# Output.net
KiCad netlist of a schematic drawn in Altium Designer
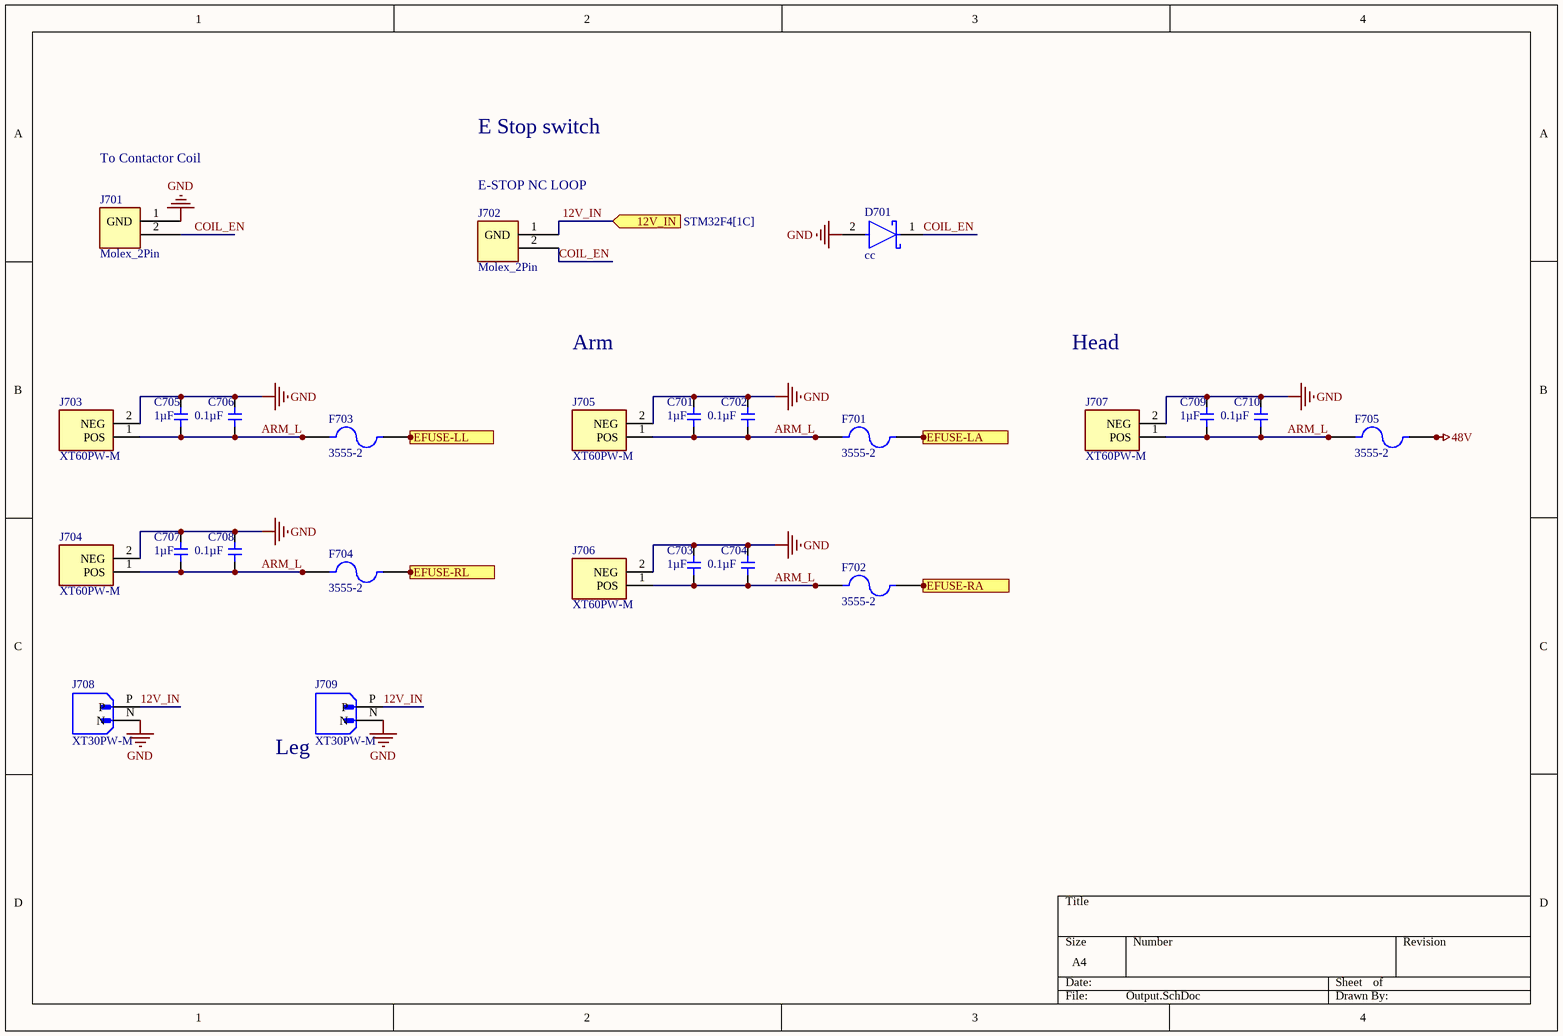
[diagram p0: Output.SchDoc]

(export (version "E")
  (design (tool "Eeschema 10.0.6"))
  (components
    (comp (ref "C701")
      (value "non-polar_Capacitor")
      (footprint "0805")
      (description "SMD type ceramic capacitor")
      (fields
        (field (name "VOLTAGE") "100V")
        (field (name "CAPACITANCE") "1µF")
        (field (name "SOURCE") "robit_passive.SchLib")
      )
      (libsource (lib "robit circuit") (part "Capacitor"))
    )
    (comp (ref "C702")
      (value "non-polar_Capacitor")
      (footprint "0603")
      (description "SMD type ceramic capacitor")
      (fields
        (field (name "VOLTAGE") "100V")
        (field (name "CAPACITANCE") "0.1µF")
        (field (name "SOURCE") "robit_passive.SchLib")
      )
      (libsource (lib "robit circuit") (part "Capacitor"))
    )
    (comp (ref "C703")
      (value "non-polar_Capacitor")
      (footprint "0805")
      (description "SMD type ceramic capacitor")
      (fields
        (field (name "VOLTAGE") "100V")
        (field (name "CAPACITANCE") "1µF")
        (field (name "SOURCE") "robit_passive.SchLib")
      )
      (libsource (lib "robit circuit") (part "Capacitor"))
    )
    (comp (ref "C704")
      (value "non-polar_Capacitor")
      (footprint "0603")
      (description "SMD type ceramic capacitor")
      (fields
        (field (name "VOLTAGE") "100V")
        (field (name "CAPACITANCE") "0.1µF")
        (field (name "SOURCE") "robit_passive.SchLib")
      )
      (libsource (lib "robit circuit") (part "Capacitor"))
    )
    (comp (ref "C705")
      (value "non-polar_Capacitor")
      (footprint "0805")
      (description "SMD type ceramic capacitor")
      (fields
        (field (name "VOLTAGE") "100V")
        (field (name "CAPACITANCE") "1µF")
        (field (name "SOURCE") "robit_passive.SchLib")
      )
      (libsource (lib "robit circuit") (part "Capacitor"))
    )
    (comp (ref "C706")
      (value "non-polar_Capacitor")
      (footprint "0603")
      (description "SMD type ceramic capacitor")
      (fields
        (field (name "VOLTAGE") "100V")
        (field (name "CAPACITANCE") "0.1µF")
        (field (name "SOURCE") "robit_passive.SchLib")
      )
      (libsource (lib "robit circuit") (part "Capacitor"))
    )
    (comp (ref "C707")
      (value "non-polar_Capacitor")
      (footprint "0805")
      (description "SMD type ceramic capacitor")
      (fields
        (field (name "VOLTAGE") "100V")
        (field (name "CAPACITANCE") "1µF")
        (field (name "SOURCE") "robit_passive.SchLib")
      )
      (libsource (lib "robit circuit") (part "Capacitor"))
    )
    (comp (ref "C708")
      (value "non-polar_Capacitor")
      (footprint "0603")
      (description "SMD type ceramic capacitor")
      (fields
        (field (name "VOLTAGE") "100V")
        (field (name "CAPACITANCE") "0.1µF")
        (field (name "SOURCE") "robit_passive.SchLib")
      )
      (libsource (lib "robit circuit") (part "Capacitor"))
    )
    (comp (ref "C709")
      (value "non-polar_Capacitor")
      (footprint "0805")
      (description "SMD type ceramic capacitor")
      (fields
        (field (name "VOLTAGE") "100V")
        (field (name "CAPACITANCE") "1µF")
        (field (name "SOURCE") "robit_passive.SchLib")
      )
      (libsource (lib "robit circuit") (part "Capacitor"))
    )
    (comp (ref "C710")
      (value "non-polar_Capacitor")
      (footprint "0603")
      (description "SMD type ceramic capacitor")
      (fields
        (field (name "VOLTAGE") "100V")
        (field (name "CAPACITANCE") "0.1µF")
        (field (name "SOURCE") "robit_passive.SchLib")
      )
      (libsource (lib "robit circuit") (part "Capacitor"))
    )
    (comp (ref "D701")
      (value "cc")
      (footprint "FP-403A-03-MFG")
      (description "Rectifier Diode, Schottky, 1 Phase, 1 Element, 5A, 100V V(RRM), Silicon")
      (libsource (lib "robit circuit") (part "1d6ec82d83fb6aee721767c19dac4b9"))
    )
    (comp (ref "F701")
      (value "3555-2")
      (footprint "FUSE_3555-2")
      (fields (field (name "MF") "Keystone Electronics"))
      (libsource (lib "3555-2 (1)") (part "3555-2"))
    )
    (comp (ref "F702")
      (value "3555-2")
      (footprint "FUSE_3555-2")
      (fields (field (name "MF") "Keystone Electronics"))
      (libsource (lib "3555-2 (1)") (part "3555-2"))
    )
    (comp (ref "F703")
      (value "3555-2")
      (footprint "FUSE_3555-2")
      (fields (field (name "MF") "Keystone Electronics"))
      (libsource (lib "3555-2 (1)") (part "3555-2"))
    )
    (comp (ref "F704")
      (value "3555-2")
      (footprint "FUSE_3555-2")
      (fields (field (name "MF") "Keystone Electronics"))
      (libsource (lib "3555-2 (1)") (part "3555-2"))
    )
    (comp (ref "F705")
      (value "3555-2")
      (footprint "FUSE_3555-2")
      (fields (field (name "MF") "Keystone Electronics"))
      (libsource (lib "3555-2 (1)") (part "3555-2"))
    )
    (comp (ref "J701")
      (value "Molex_2Pin")
      (footprint "MOLEX_2PIN")
      (description "Molex 2Pin Connector")
      (fields (field (name "SOURCE") "robit_connector.SchLib"))
      (libsource (lib "robit circuit") (part "Molex_2Pin"))
    )
    (comp (ref "J702")
      (value "Molex_2Pin")
      (footprint "MOLEX_2PIN")
      (description "Molex 2Pin Connector")
      (fields (field (name "SOURCE") "robit_connector.SchLib"))
      (libsource (lib "robit circuit") (part "Molex_2Pin"))
    )
    (comp (ref "J703")
      (value "XT60PW-M")
      (footprint "XT60PW-M")
      (description "Socket, DC supply, male, PIN: 2")
      (fields (field (name "MF") "AMASS") (field (name "SOURCE") "robit_connector.SchLib"))
      (libsource (lib "robit circuit") (part "XT60PW-M"))
    )
    (comp (ref "J704")
      (value "XT60PW-M")
      (footprint "XT60PW-M")
      (description "Socket, DC supply, male, PIN: 2")
      (fields (field (name "MF") "AMASS") (field (name "SOURCE") "robit_connector.SchLib"))
      (libsource (lib "robit circuit") (part "XT60PW-M"))
    )
    (comp (ref "J705")
      (value "XT60PW-M")
      (footprint "XT60PW-M")
      (description "Socket, DC supply, male, PIN: 2")
      (fields (field (name "MF") "AMASS") (field (name "SOURCE") "robit_connector.SchLib"))
      (libsource (lib "robit circuit") (part "XT60PW-M"))
    )
    (comp (ref "J706")
      (value "XT60PW-M")
      (footprint "XT60PW-M")
      (description "Socket, DC supply, male, PIN: 2")
      (fields (field (name "MF") "AMASS") (field (name "SOURCE") "robit_connector.SchLib"))
      (libsource (lib "robit circuit") (part "XT60PW-M"))
    )
    (comp (ref "J707")
      (value "XT60PW-M")
      (footprint "XT60PW-M")
      (description "Socket, DC supply, male, PIN: 2")
      (fields (field (name "MF") "AMASS") (field (name "SOURCE") "robit_connector.SchLib"))
      (libsource (lib "robit circuit") (part "XT60PW-M"))
    )
    (comp (ref "J708")
      (value "XT30PW-M")
      (footprint "AMASS_XT30PW-M")
      (description "Socket; DC supply; XT30; male; PIN: 2; on PCBs; THT; Colour: yellow")
      (fields (field (name "MF") "AMASS"))
      (libsource (lib "robit circuit") (part "XT30PW-M"))
    )
    (comp (ref "J709")
      (value "XT30PW-M")
      (footprint "AMASS_XT30PW-M")
      (description "Socket; DC supply; XT30; male; PIN: 2; on PCBs; THT; Colour: yellow")
      (fields (field (name "MF") "AMASS"))
      (libsource (lib "robit circuit") (part "XT30PW-M"))
    )
  )
  (nets
    (net (code "1") (name "/12V_IN") (class "Default")
      (node (ref "J702") (pin "1") (pinfunction "GND_1") (pintype "passive"))
      (node (ref "J708") (pin "P") (pinfunction "P_P") (pintype "passive"))
      (node (ref "J709") (pin "P") (pinfunction "P_P") (pintype "passive"))
    )
    (net (code "2") (name "/ARM_L") (class "Default")
      (node (ref "C701") (pin "1") (pinfunction "1_1") (pintype "passive"))
      (node (ref "C702") (pin "1") (pinfunction "1_1") (pintype "passive"))
      (node (ref "C703") (pin "1") (pinfunction "1_1") (pintype "passive"))
      (node (ref "C704") (pin "1") (pinfunction "1_1") (pintype "passive"))
      (node (ref "C705") (pin "1") (pinfunction "1_1") (pintype "passive"))
      (node (ref "C706") (pin "1") (pinfunction "1_1") (pintype "passive"))
      (node (ref "C707") (pin "1") (pinfunction "1_1") (pintype "passive"))
      (node (ref "C708") (pin "1") (pinfunction "1_1") (pintype "passive"))
      (node (ref "C709") (pin "1") (pinfunction "1_1") (pintype "passive"))
      (node (ref "C710") (pin "1") (pinfunction "1_1") (pintype "passive"))
      (node (ref "F701") (pin "1_1") (pinfunction "1_1_1") (pintype "passive"))
      (node (ref "F701") (pin "1_2") (pinfunction "1_1_2") (pintype "passive"))
      (node (ref "F702") (pin "1_1") (pinfunction "1_1_1") (pintype "passive"))
      (node (ref "F702") (pin "1_2") (pinfunction "1_1_2") (pintype "passive"))
      (node (ref "F703") (pin "1_1") (pinfunction "1_1_1") (pintype "passive"))
      (node (ref "F703") (pin "1_2") (pinfunction "1_1_2") (pintype "passive"))
      (node (ref "F704") (pin "1_1") (pinfunction "1_1_1") (pintype "passive"))
      (node (ref "F704") (pin "1_2") (pinfunction "1_1_2") (pintype "passive"))
      (node (ref "F705") (pin "1_1") (pinfunction "1_1_1") (pintype "passive"))
      (node (ref "F705") (pin "1_2") (pinfunction "1_1_2") (pintype "passive"))
      (node (ref "J703") (pin "1") (pinfunction "POS_1") (pintype "passive"))
      (node (ref "J704") (pin "1") (pinfunction "POS_1") (pintype "passive"))
      (node (ref "J705") (pin "1") (pinfunction "POS_1") (pintype "passive"))
      (node (ref "J706") (pin "1") (pinfunction "POS_1") (pintype "passive"))
      (node (ref "J707") (pin "1") (pinfunction "POS_1") (pintype "passive"))
    )
    (net (code "3") (name "/COIL_EN") (class "Default")
      (node (ref "D701") (pin "1") (pinfunction "C_1") (pintype "passive"))
      (node (ref "J701") (pin "2") (pintype "passive"))
      (node (ref "J702") (pin "2") (pintype "passive"))
    )
    (net (code "4") (name "/EFUSE-LA") (class "Default")
      (node (ref "F701") (pin "2_1") (pinfunction "2_2_1") (pintype "passive"))
      (node (ref "F701") (pin "2_2") (pinfunction "2_2_2") (pintype "passive"))
    )
    (net (code "5") (name "/EFUSE-LL") (class "Default")
      (node (ref "F703") (pin "2_1") (pinfunction "2_2_1") (pintype "passive"))
      (node (ref "F703") (pin "2_2") (pinfunction "2_2_2") (pintype "passive"))
    )
    (net (code "6") (name "/EFUSE-RA") (class "Default")
      (node (ref "F702") (pin "2_1") (pinfunction "2_2_1") (pintype "passive"))
      (node (ref "F702") (pin "2_2") (pinfunction "2_2_2") (pintype "passive"))
    )
    (net (code "7") (name "/EFUSE-RL") (class "Default")
      (node (ref "F704") (pin "2_1") (pinfunction "2_2_1") (pintype "passive"))
      (node (ref "F704") (pin "2_2") (pinfunction "2_2_2") (pintype "passive"))
    )
    (net (code "8") (name "48V") (class "Default")
      (node (ref "F705") (pin "2_1") (pinfunction "2_2_1") (pintype "passive"))
      (node (ref "F705") (pin "2_2") (pinfunction "2_2_2") (pintype "passive"))
    )
    (net (code "9") (name "GND") (class "Default")
      (node (ref "C701") (pin "2") (pinfunction "2_2") (pintype "passive"))
      (node (ref "C702") (pin "2") (pinfunction "2_2") (pintype "passive"))
      (node (ref "C703") (pin "2") (pinfunction "2_2") (pintype "passive"))
      (node (ref "C704") (pin "2") (pinfunction "2_2") (pintype "passive"))
      (node (ref "C705") (pin "2") (pinfunction "2_2") (pintype "passive"))
      (node (ref "C706") (pin "2") (pinfunction "2_2") (pintype "passive"))
      (node (ref "C707") (pin "2") (pinfunction "2_2") (pintype "passive"))
      (node (ref "C708") (pin "2") (pinfunction "2_2") (pintype "passive"))
      (node (ref "C709") (pin "2") (pinfunction "2_2") (pintype "passive"))
      (node (ref "C710") (pin "2") (pinfunction "2_2") (pintype "passive"))
      (node (ref "D701") (pin "2") (pinfunction "A_2") (pintype "passive"))
      (node (ref "J701") (pin "1") (pinfunction "GND_1") (pintype "passive"))
      (node (ref "J703") (pin "2") (pinfunction "NEG_2") (pintype "passive"))
      (node (ref "J704") (pin "2") (pinfunction "NEG_2") (pintype "passive"))
      (node (ref "J705") (pin "2") (pinfunction "NEG_2") (pintype "passive"))
      (node (ref "J706") (pin "2") (pinfunction "NEG_2") (pintype "passive"))
      (node (ref "J707") (pin "2") (pinfunction "NEG_2") (pintype "passive"))
      (node (ref "J708") (pin "N") (pinfunction "N_N") (pintype "power_in"))
      (node (ref "J709") (pin "N") (pinfunction "N_N") (pintype "power_in"))
    )
  )
)
